# 1u_debug_breakout.net
KiCad netlist of a schematic drawn in EAGLE
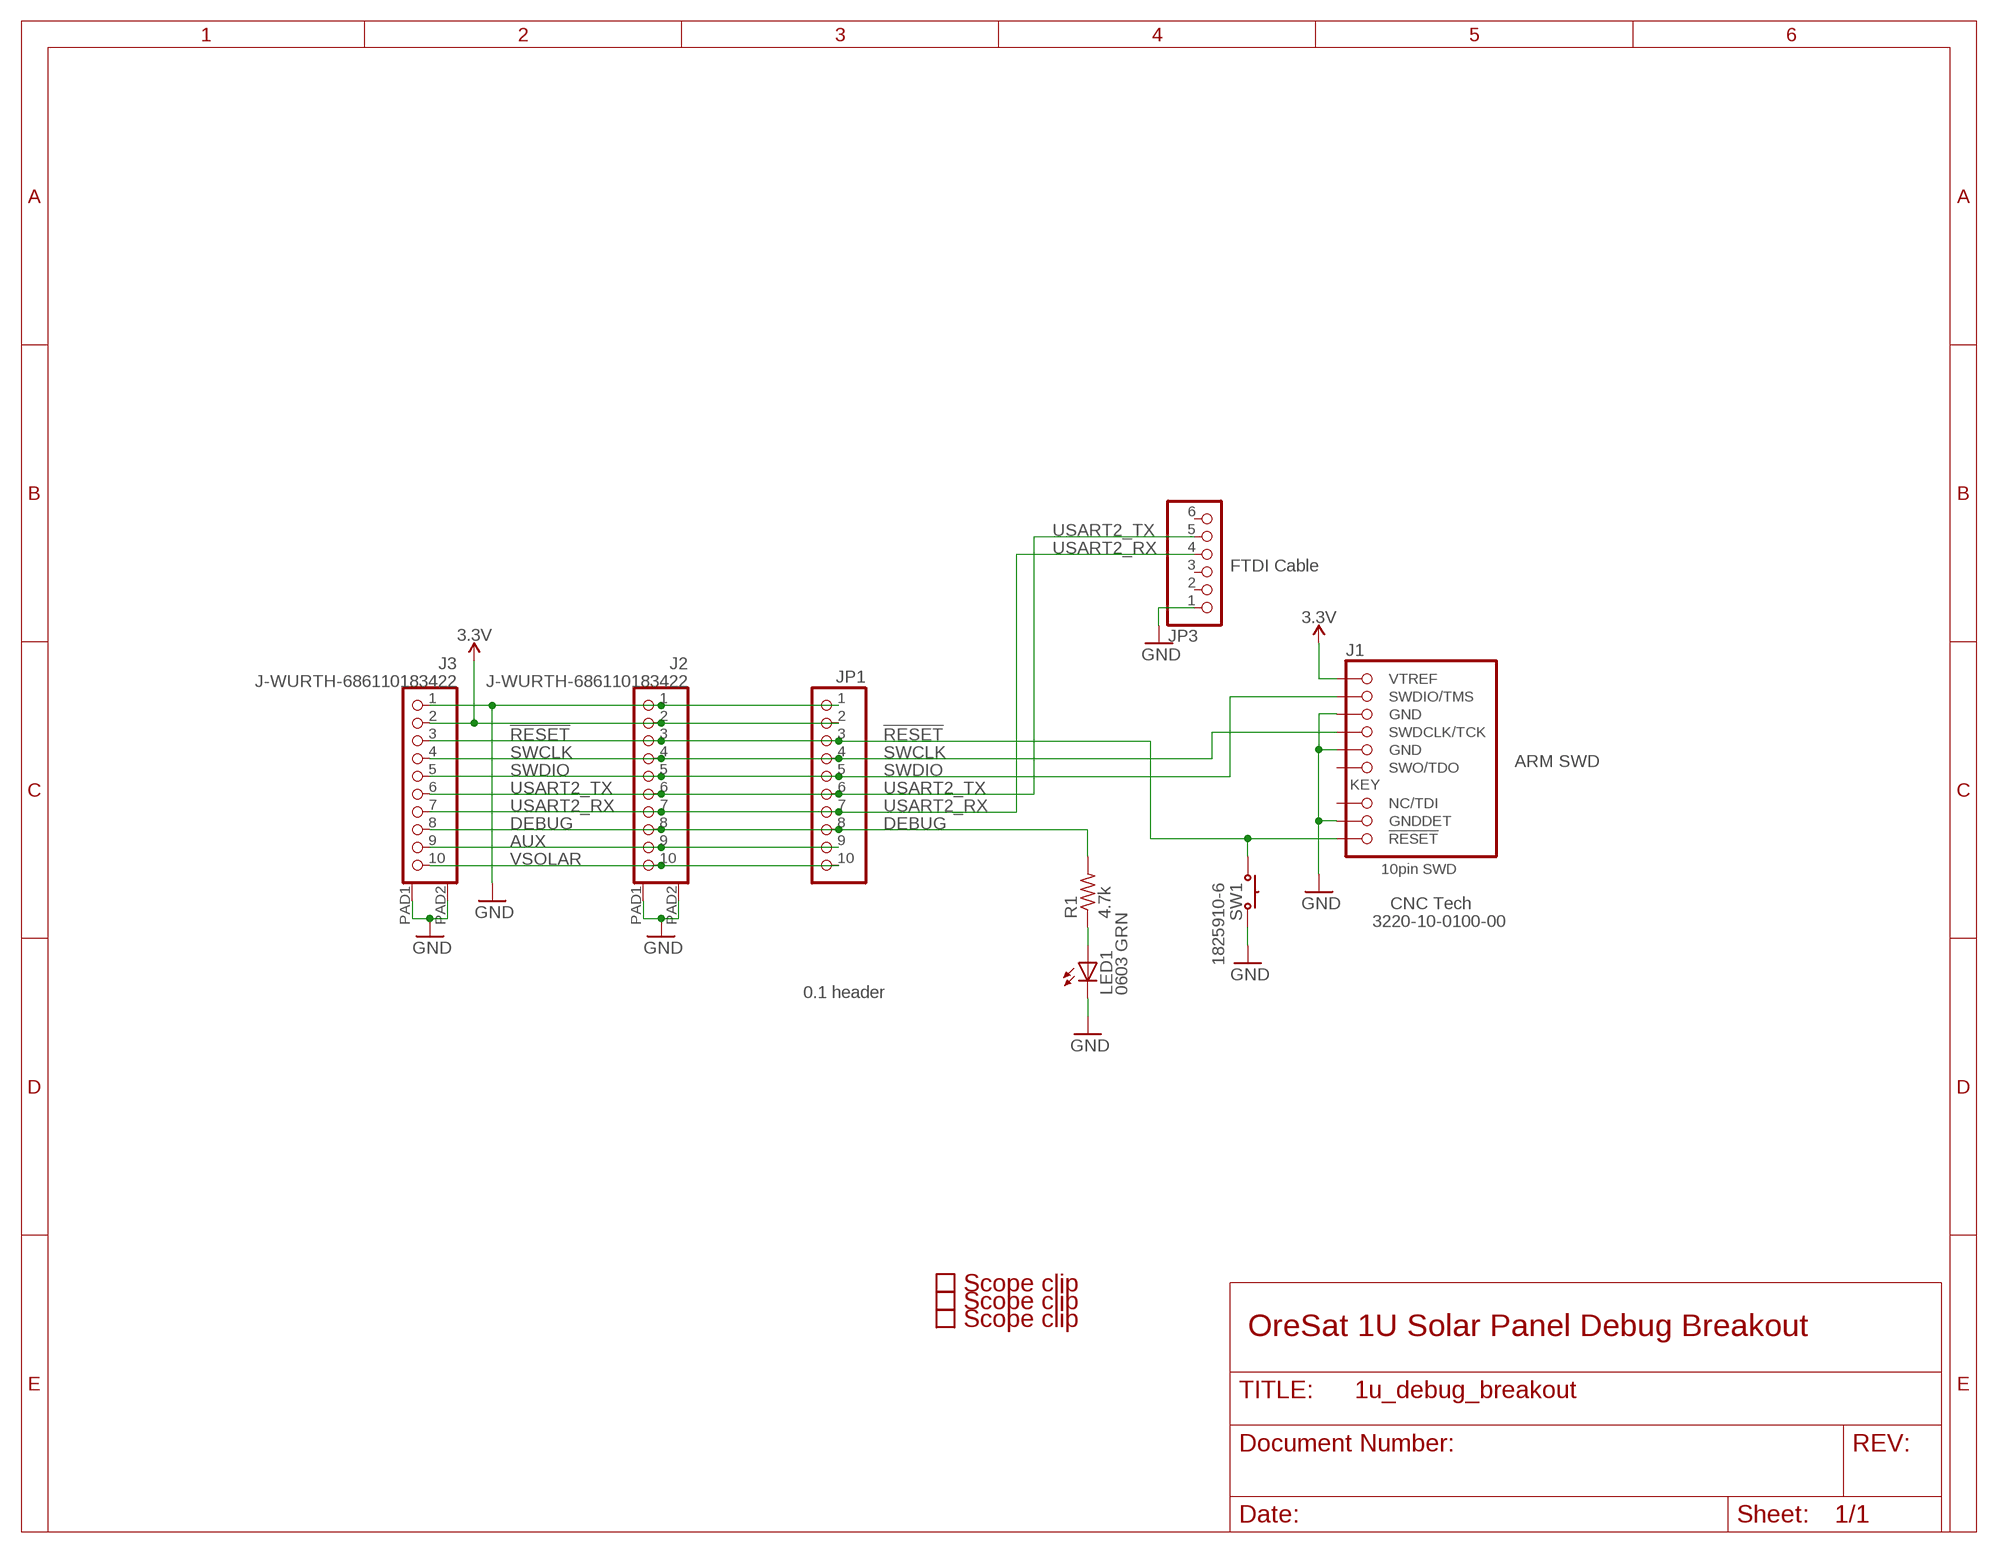
[diagram p0: schematic, sheet 1]

(export (version "E")
  (design (tool "Eeschema 10.0.6"))
  (components
    (comp (ref "J1")
      (value "1.27MM-SWD-CONNECTOR")
      (footprint "eagle-import:1.27MM_2X5")
      (fields (field (name "MFR") "CNC Tech") (field (name "MPN") "3220-10-0100-00"))
      (libsource (lib "eagle-import") (part "1.27MM-SWD-CONNECTOR"))
    )
    (comp (ref "J2")
      (value "J-WURTH-686110183422")
      (footprint "eagle-import:J-WURTH-686110183422")
      (libsource (lib "eagle-import") (part "J-WURTH-686110183422"))
    )
    (comp (ref "J3")
      (value "J-WURTH-686110183422")
      (footprint "eagle-import:J-WURTH-686110183422")
      (libsource (lib "eagle-import") (part "J-WURTH-686110183422"))
    )
    (comp (ref "JP1")
      (value "PINHD-1X10")
      (footprint "eagle-import:1X10")
      (libsource (lib "eagle-import") (part "PINHD-1X10"))
    )
    (comp (ref "JP3")
      (value "PINHD-1X6")
      (footprint "eagle-import:1X06")
      (libsource (lib "eagle-import") (part "PINHD-1X6"))
    )
    (comp (ref "LED1")
      (value "0603 GRN")
      (footprint "eagle-import:CHIPLED_0603")
      (libsource (lib "eagle-import") (part "LEDCHIPLED_0603"))
    )
    (comp (ref "R1")
      (value "4.7k")
      (footprint "eagle-import:R0603")
      (libsource (lib "eagle-import") (part "R-US_R0603"))
    )
    (comp (ref "SW1")
      (value "1825910-6")
      (footprint "eagle-import:SWITCH_FSM4JAH")
      (libsource (lib "eagle-import") (part "1825910-6"))
    )
    (comp (ref "U$1")
      (value "SCOPE_CLIP")
      (footprint "eagle-import:SCOPE_CLIP")
      (libsource (lib "eagle-import") (part "SCOPE_CLIP"))
    )
    (comp (ref "U$2")
      (value "SCOPE_CLIP")
      (footprint "eagle-import:SCOPE_CLIP")
      (libsource (lib "eagle-import") (part "SCOPE_CLIP"))
    )
    (comp (ref "U$3")
      (value "SCOPE_CLIP")
      (footprint "eagle-import:SCOPE_CLIP")
      (libsource (lib "eagle-import") (part "SCOPE_CLIP"))
    )
  )
  (nets
    (net (code "1") (name "/AUX") (class "Default")
      (node (ref "J2") (pin "9") (pinfunction "9_9") (pintype "passive"))
      (node (ref "J3") (pin "9") (pinfunction "9_9") (pintype "passive"))
      (node (ref "JP1") (pin "9") (pinfunction "9_9") (pintype "passive"))
    )
    (net (code "2") (name "/DEBUG") (class "Default")
      (node (ref "J2") (pin "8") (pinfunction "8_8") (pintype "passive"))
      (node (ref "J3") (pin "8") (pinfunction "8_8") (pintype "passive"))
      (node (ref "JP1") (pin "8") (pinfunction "8_8") (pintype "passive"))
      (node (ref "R1") (pin "2") (pinfunction "2_2") (pintype "passive"))
    )
    (net (code "3") (name "/SWCLK") (class "Default")
      (node (ref "J1") (pin "SWDCLK") (pinfunction "SWDCLK/TCK_SWDCLK") (pintype "passive"))
      (node (ref "J2") (pin "4") (pinfunction "4_4") (pintype "passive"))
      (node (ref "J3") (pin "4") (pinfunction "4_4") (pintype "passive"))
      (node (ref "JP1") (pin "4") (pinfunction "4_4") (pintype "passive"))
    )
    (net (code "4") (name "/SWDIO") (class "Default")
      (node (ref "J1") (pin "SWDIO") (pinfunction "SWDIO/TMS_SWDIO") (pintype "passive"))
      (node (ref "J2") (pin "5") (pinfunction "5_5") (pintype "passive"))
      (node (ref "J3") (pin "5") (pinfunction "5_5") (pintype "passive"))
      (node (ref "JP1") (pin "5") (pinfunction "5_5") (pintype "passive"))
    )
    (net (code "5") (name "/USART2_RX") (class "Default")
      (node (ref "J2") (pin "7") (pinfunction "7_7") (pintype "passive"))
      (node (ref "J3") (pin "7") (pinfunction "7_7") (pintype "passive"))
      (node (ref "JP1") (pin "7") (pinfunction "7_7") (pintype "passive"))
      (node (ref "JP3") (pin "4") (pinfunction "4_4") (pintype "passive"))
    )
    (net (code "6") (name "/USART2_TX") (class "Default")
      (node (ref "J2") (pin "6") (pinfunction "6_6") (pintype "passive"))
      (node (ref "J3") (pin "6") (pinfunction "6_6") (pintype "passive"))
      (node (ref "JP1") (pin "6") (pinfunction "6_6") (pintype "passive"))
      (node (ref "JP3") (pin "5") (pinfunction "5_5") (pintype "passive"))
    )
    (net (code "7") (name "/VSOLAR") (class "Default")
      (node (ref "J2") (pin "10") (pinfunction "10_10") (pintype "passive"))
      (node (ref "J3") (pin "10") (pinfunction "10_10") (pintype "passive"))
      (node (ref "JP1") (pin "10") (pinfunction "10_10") (pintype "passive"))
    )
    (net (code "8") (name "/~{RESET}") (class "Default")
      (node (ref "J1") (pin "!RESET") (pinfunction "~{RESET}_!RESET") (pintype "passive"))
      (node (ref "J2") (pin "3") (pinfunction "3_3") (pintype "passive"))
      (node (ref "J3") (pin "3") (pinfunction "3_3") (pintype "passive"))
      (node (ref "JP1") (pin "3") (pinfunction "3_3") (pintype "passive"))
      (node (ref "SW1") (pin "1") (pinfunction "1_1") (pintype "passive"))
      (node (ref "SW1") (pin "2") (pinfunction "1_2") (pintype "passive"))
    )
    (net (code "9") (name "3.3V") (class "Default")
      (node (ref "J1") (pin "VTREF") (pinfunction "VTREF_VTREF") (pintype "passive"))
      (node (ref "J2") (pin "2") (pinfunction "2_2") (pintype "passive"))
      (node (ref "J3") (pin "2") (pinfunction "2_2") (pintype "passive"))
      (node (ref "JP1") (pin "2") (pinfunction "2_2") (pintype "passive"))
    )
    (net (code "10") (name "GND") (class "Default")
      (node (ref "J1") (pin "GND") (pinfunction "GND_GND") (pintype "passive"))
      (node (ref "J1") (pin "GND@2") (pinfunction "GND_GND@2") (pintype "passive"))
      (node (ref "J1") (pin "GNDDET") (pinfunction "GNDDET_GNDDET") (pintype "passive"))
      (node (ref "J2") (pin "1") (pinfunction "1_1") (pintype "passive"))
      (node (ref "J2") (pin "PAD1") (pinfunction "PAD1_PAD1") (pintype "passive"))
      (node (ref "J2") (pin "PAD2") (pinfunction "PAD2_PAD2") (pintype "passive"))
      (node (ref "J3") (pin "1") (pinfunction "1_1") (pintype "passive"))
      (node (ref "J3") (pin "PAD1") (pinfunction "PAD1_PAD1") (pintype "passive"))
      (node (ref "J3") (pin "PAD2") (pinfunction "PAD2_PAD2") (pintype "passive"))
      (node (ref "JP1") (pin "1") (pinfunction "1_1") (pintype "passive"))
      (node (ref "JP3") (pin "1") (pinfunction "1_1") (pintype "passive"))
      (node (ref "LED1") (pin "C") (pinfunction "C_C") (pintype "passive"))
      (node (ref "SW1") (pin "3") (pinfunction "2_3") (pintype "passive"))
      (node (ref "SW1") (pin "4") (pinfunction "2_4") (pintype "passive"))
    )
    (net (code "11") (name "Net-(LED1-PadA)") (class "Default")
      (node (ref "LED1") (pin "A") (pinfunction "A_A") (pintype "passive"))
      (node (ref "R1") (pin "1") (pinfunction "1_1") (pintype "passive"))
    )
    (net (code "12") (name "unconnected-(J1-NC{slash}TDI-PadNC)") (class "Default")
      (node (ref "J1") (pin "NC") (pinfunction "NC/TDI_NC") (pintype "passive"))
    )
    (net (code "13") (name "unconnected-(J1-SWO{slash}TDO-PadSWO)") (class "Default")
      (node (ref "J1") (pin "SWO") (pinfunction "SWO/TDO_SWO") (pintype "passive"))
    )
    (net (code "14") (name "unconnected-(JP3-Pad2)") (class "Default")
      (node (ref "JP3") (pin "2") (pinfunction "2_2") (pintype "passive"))
    )
    (net (code "15") (name "unconnected-(JP3-Pad3)") (class "Default")
      (node (ref "JP3") (pin "3") (pinfunction "3_3") (pintype "passive"))
    )
    (net (code "16") (name "unconnected-(JP3-Pad6)") (class "Default")
      (node (ref "JP3") (pin "6") (pinfunction "6_6") (pintype "passive"))
    )
  )
)
